# motordriver-v4_0_power-stage.net
KiCad netlist of a schematic drawn in Altium Designer
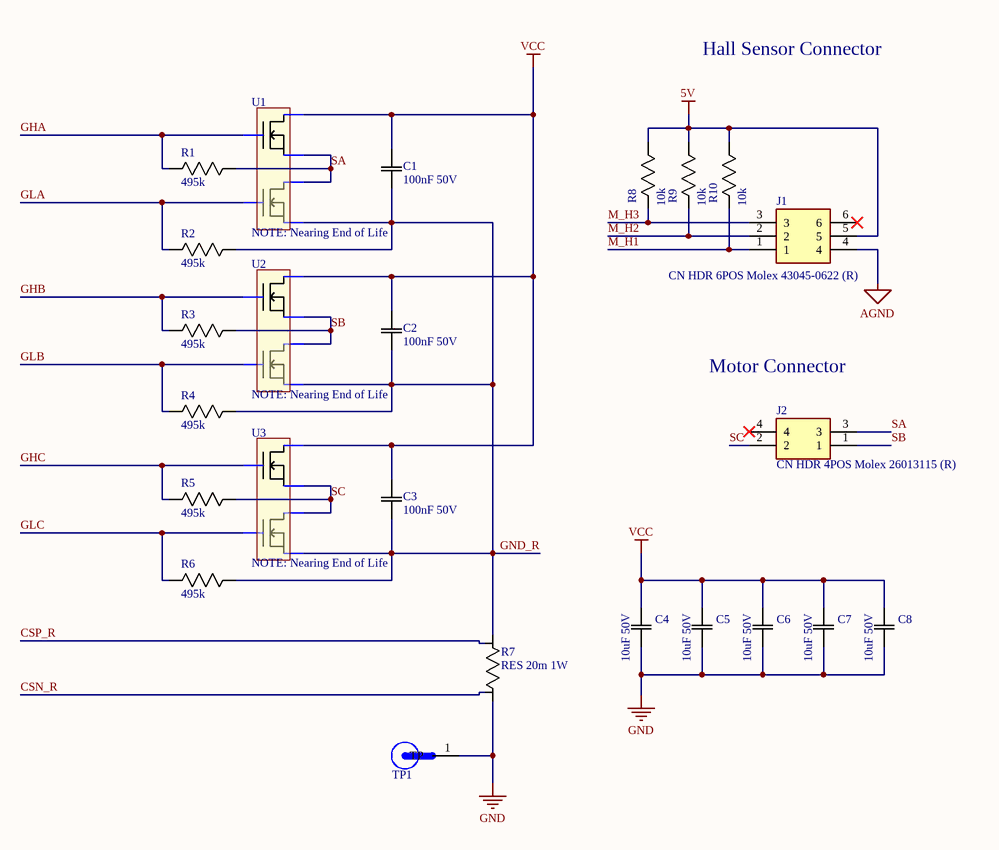
[diagram p0: motordriver-v4.0_power-stage.SchDoc]

(export (version "E")
  (design (tool "Eeschema 10.0.6"))
  (components
    (comp (ref "C1")
      (value "100nF 50V")
      (footprint "0603")
      (description "CAP CER 0.1UF 50V X7R 0805")
      (fields (field (name "TOLERANCE") "10%"))
      (libsource (lib "AltiumLibraries") (part "CAP 100nF 50V"))
    )
    (comp (ref "C2")
      (value "100nF 50V")
      (footprint "0603")
      (description "CAP CER 0.1UF 50V X7R 0805")
      (fields (field (name "TOLERANCE") "10%"))
      (libsource (lib "AltiumLibraries") (part "CAP 100nF 50V"))
    )
    (comp (ref "C3")
      (value "100nF 50V")
      (footprint "0603")
      (description "CAP CER 0.1UF 50V X7R 0805")
      (fields (field (name "TOLERANCE") "10%"))
      (libsource (lib "AltiumLibraries") (part "CAP 100nF 50V"))
    )
    (comp (ref "C4")
      (value "10uF 50V")
      (footprint "0805")
      (description "CAP CER 10UF 50V X7R")
      (fields (field (name "TOLERANCE") "10%"))
      (libsource (lib "AltiumLibraries") (part "CAP 10uF 50V"))
    )
    (comp (ref "C5")
      (value "10uF 50V")
      (footprint "0805")
      (description "CAP CER 10UF 50V X7R")
      (fields (field (name "TOLERANCE") "10%"))
      (libsource (lib "AltiumLibraries") (part "CAP 10uF 50V"))
    )
    (comp (ref "C6")
      (value "10uF 50V")
      (footprint "0805")
      (description "CAP CER 10UF 50V X7R")
      (fields (field (name "TOLERANCE") "10%"))
      (libsource (lib "AltiumLibraries") (part "CAP 10uF 50V"))
    )
    (comp (ref "C7")
      (value "10uF 50V")
      (footprint "0805")
      (description "CAP CER 10UF 50V X7R")
      (fields (field (name "TOLERANCE") "10%"))
      (libsource (lib "AltiumLibraries") (part "CAP 10uF 50V"))
    )
    (comp (ref "C8")
      (value "10uF 50V")
      (footprint "0805")
      (description "CAP CER 10UF 50V X7R")
      (fields (field (name "TOLERANCE") "10%"))
      (libsource (lib "AltiumLibraries") (part "CAP 10uF 50V"))
    )
    (comp (ref "J1")
      (value "CN HDR 6POS Molex 43045-0622 (R)")
      (footprint "430450622")
      (description "Molex 43045-0622 6POS Microfit\r\ndual row, right angle")
      (libsource (lib "AltiumLibraries") (part "CN HDR 6POS Molex 43045-0622 (R)"))
    )
    (comp (ref "J2")
      (value "CN HDR 4POS Molex 26013115 (R)")
      (footprint "26013115")
      (description "Molex 26013115 4POS Minifit\r\ndual row, right angle")
      (libsource (lib "AltiumLibraries") (part "CN HDR 4POS Molex 26013115 (R)"))
    )
    (comp (ref "R1")
      (value "495k")
      (footprint "0603")
      (description "RES SMD 499K OHM 1% 1/8W 0805")
      (fields
        (field (name "MANUFACTURER") "Yageo")
        (field (name "MANUFACTURER PART NUMBER") "RC0805FR-07499KL")
      )
      (libsource (lib "AltiumLibraries") (part "RES 495k 1/8W"))
    )
    (comp (ref "R2")
      (value "495k")
      (footprint "0603")
      (description "RES SMD 499K OHM 1% 1/8W 0805")
      (fields
        (field (name "MANUFACTURER") "Yageo")
        (field (name "MANUFACTURER PART NUMBER") "RC0805FR-07499KL")
      )
      (libsource (lib "AltiumLibraries") (part "RES 495k 1/8W"))
    )
    (comp (ref "R3")
      (value "495k")
      (footprint "0603")
      (description "RES SMD 499K OHM 1% 1/8W 0805")
      (fields
        (field (name "MANUFACTURER") "Yageo")
        (field (name "MANUFACTURER PART NUMBER") "RC0805FR-07499KL")
      )
      (libsource (lib "AltiumLibraries") (part "RES 495k 1/8W"))
    )
    (comp (ref "R4")
      (value "495k")
      (footprint "0603")
      (description "RES SMD 499K OHM 1% 1/8W 0805")
      (fields
        (field (name "MANUFACTURER") "Yageo")
        (field (name "MANUFACTURER PART NUMBER") "RC0805FR-07499KL")
      )
      (libsource (lib "AltiumLibraries") (part "RES 495k 1/8W"))
    )
    (comp (ref "R5")
      (value "495k")
      (footprint "0603")
      (description "RES SMD 499K OHM 1% 1/8W 0805")
      (fields
        (field (name "MANUFACTURER") "Yageo")
        (field (name "MANUFACTURER PART NUMBER") "RC0805FR-07499KL")
      )
      (libsource (lib "AltiumLibraries") (part "RES 495k 1/8W"))
    )
    (comp (ref "R6")
      (value "495k")
      (footprint "0603")
      (description "RES SMD 499K OHM 1% 1/8W 0805")
      (fields
        (field (name "MANUFACTURER") "Yageo")
        (field (name "MANUFACTURER PART NUMBER") "RC0805FR-07499KL")
      )
      (libsource (lib "AltiumLibraries") (part "RES 495k 1/8W"))
    )
    (comp (ref "R7")
      (value "RES 20m 1W")
      (footprint "1206 - Sense")
      (description "RES SMD 0.02 OHM 1% 1W 1206")
      (libsource (lib "AltiumLibraries") (part "RES 20m 1W"))
    )
    (comp (ref "R8")
      (value "10k")
      (footprint "0603")
      (description "RES SMD 10K OHM 1% 1/8W 0805")
      (fields (field (name "TOLERANCE") "1%"))
      (libsource (lib "") (part "RES 10k 1/8W - 1%_1"))
    )
    (comp (ref "R9")
      (value "10k")
      (footprint "0603")
      (description "RES SMD 10K OHM 1% 1/8W 0805")
      (fields (field (name "TOLERANCE") "1%"))
      (libsource (lib "AltiumLibraries") (part "RES 10k 1/8W - 1%"))
    )
    (comp (ref "R10")
      (value "10k")
      (footprint "0603")
      (description "RES SMD 10K OHM 1% 1/8W 0805")
      (fields (field (name "TOLERANCE") "1%"))
      (libsource (lib "AltiumLibraries") (part "RES 10k 1/8W - 1%"))
    )
    (comp (ref "TP1")
      (value "Test Point - 5019")
      (footprint "TP380X203")
      (description "PC Test Point, Miniature Phosphor Bronze, Silver Plating Surface Mount Mounting Type")
      (fields (field (name "MP") "5019") (field (name "MF") "Keystone Electronics"))
      (libsource (lib "AltiumLibraries") (part "Test Point - 5019"))
    )
    (comp (ref "U1")
      (value "NOTE: Nearing End of Life")
      (footprint "PG-TDSON-8-10")
      (description "MOSFET N+N 60V 20A")
      (fields (field (name "MF") "Infineon Technologies"))
      (libsource (lib "AltiumLibraries") (part "MOSFET IPG20N06S4-15A"))
    )
    (comp (ref "U2")
      (value "NOTE: Nearing End of Life")
      (footprint "PG-TDSON-8-10")
      (description "MOSFET N+N 60V 20A")
      (fields (field (name "MF") "Infineon Technologies"))
      (libsource (lib "AltiumLibraries") (part "MOSFET IPG20N06S4-15A"))
    )
    (comp (ref "U3")
      (value "NOTE: Nearing End of Life")
      (footprint "PG-TDSON-8-10")
      (description "MOSFET N+N 60V 20A")
      (fields (field (name "MF") "Infineon Technologies"))
      (libsource (lib "AltiumLibraries") (part "MOSFET IPG20N06S4-15A"))
    )
  )
  (nets
    (net (code "1") (name "/CSN_R") (class "Default")
      (node (ref "R7") (pin "4") (pinfunction "4_4") (pintype "passive"))
    )
    (net (code "2") (name "/CSP_R") (class "Default")
      (node (ref "R7") (pin "3") (pinfunction "3_3") (pintype "passive"))
    )
    (net (code "3") (name "/GHA") (class "Default")
      (node (ref "R1") (pin "2") (pinfunction "R2_2") (pintype "passive"))
      (node (ref "U1") (pin "2") (pinfunction "G1_2") (pintype "passive"))
    )
    (net (code "4") (name "/GHB") (class "Default")
      (node (ref "R3") (pin "2") (pinfunction "R2_2") (pintype "passive"))
      (node (ref "U2") (pin "2") (pinfunction "G1_2") (pintype "passive"))
    )
    (net (code "5") (name "/GHC") (class "Default")
      (node (ref "R5") (pin "2") (pinfunction "R2_2") (pintype "passive"))
      (node (ref "U3") (pin "2") (pinfunction "G1_2") (pintype "passive"))
    )
    (net (code "6") (name "/GLA") (class "Default")
      (node (ref "R2") (pin "2") (pinfunction "R2_2") (pintype "passive"))
      (node (ref "U1") (pin "4") (pinfunction "G2_4") (pintype "passive"))
    )
    (net (code "7") (name "/GLB") (class "Default")
      (node (ref "R4") (pin "2") (pinfunction "R2_2") (pintype "passive"))
      (node (ref "U2") (pin "4") (pinfunction "G2_4") (pintype "passive"))
    )
    (net (code "8") (name "/GLC") (class "Default")
      (node (ref "R6") (pin "2") (pinfunction "R2_2") (pintype "passive"))
      (node (ref "U3") (pin "4") (pinfunction "G2_4") (pintype "passive"))
    )
    (net (code "9") (name "/GND_R") (class "Default")
      (node (ref "C1") (pin "1") (pinfunction "C1_1") (pintype "passive"))
      (node (ref "C2") (pin "1") (pinfunction "C1_1") (pintype "passive"))
      (node (ref "C3") (pin "1") (pinfunction "C1_1") (pintype "passive"))
      (node (ref "R2") (pin "1") (pinfunction "R1_1") (pintype "passive"))
      (node (ref "R4") (pin "1") (pinfunction "R1_1") (pintype "passive"))
      (node (ref "R6") (pin "1") (pinfunction "R1_1") (pintype "passive"))
      (node (ref "R7") (pin "1") (pinfunction "R1_1") (pintype "passive"))
      (node (ref "U1") (pin "3") (pinfunction "S2_3") (pintype "passive"))
      (node (ref "U2") (pin "3") (pinfunction "S2_3") (pintype "passive"))
      (node (ref "U3") (pin "3") (pinfunction "S2_3") (pintype "passive"))
    )
    (net (code "10") (name "/M_H1") (class "Default")
      (node (ref "J1") (pin "1") (pinfunction "1_1") (pintype "passive"))
      (node (ref "R10") (pin "2") (pinfunction "R2_2") (pintype "passive"))
    )
    (net (code "11") (name "/M_H2") (class "Default")
      (node (ref "J1") (pin "2") (pinfunction "2_2") (pintype "passive"))
      (node (ref "R9") (pin "2") (pinfunction "R2_2") (pintype "passive"))
    )
    (net (code "12") (name "/M_H3") (class "Default")
      (node (ref "J1") (pin "3") (pinfunction "3_3") (pintype "passive"))
      (node (ref "R8") (pin "2") (pinfunction "R2_2") (pintype "passive"))
    )
    (net (code "13") (name "/SA") (class "Default")
      (node (ref "J2") (pin "3") (pinfunction "3_3") (pintype "passive"))
      (node (ref "R1") (pin "1") (pinfunction "R1_1") (pintype "passive"))
      (node (ref "U1") (pin "1") (pinfunction "S1_1") (pintype "passive"))
      (node (ref "U1") (pin "6") (pinfunction "D2_6") (pintype "passive"))
    )
    (net (code "14") (name "/SB") (class "Default")
      (node (ref "J2") (pin "1") (pinfunction "1_1") (pintype "passive"))
      (node (ref "R3") (pin "1") (pinfunction "R1_1") (pintype "passive"))
      (node (ref "U2") (pin "1") (pinfunction "S1_1") (pintype "passive"))
      (node (ref "U2") (pin "6") (pinfunction "D2_6") (pintype "passive"))
    )
    (net (code "15") (name "/SC") (class "Default")
      (node (ref "J2") (pin "2") (pinfunction "2_2") (pintype "passive"))
      (node (ref "R5") (pin "1") (pinfunction "R1_1") (pintype "passive"))
      (node (ref "U3") (pin "1") (pinfunction "S1_1") (pintype "passive"))
      (node (ref "U3") (pin "6") (pinfunction "D2_6") (pintype "passive"))
    )
    (net (code "16") (name "5V") (class "Default")
      (node (ref "J1") (pin "5") (pinfunction "5_5") (pintype "passive"))
      (node (ref "R10") (pin "1") (pinfunction "R1_1") (pintype "passive"))
      (node (ref "R8") (pin "1") (pinfunction "R1_1") (pintype "passive"))
      (node (ref "R9") (pin "1") (pinfunction "R1_1") (pintype "passive"))
    )
    (net (code "17") (name "AGND") (class "Default")
      (node (ref "J1") (pin "4") (pinfunction "4_4") (pintype "passive"))
    )
    (net (code "18") (name "GND") (class "Default")
      (node (ref "C4") (pin "2") (pinfunction "C2_2") (pintype "passive"))
      (node (ref "C5") (pin "2") (pinfunction "C2_2") (pintype "passive"))
      (node (ref "C6") (pin "2") (pinfunction "C2_2") (pintype "passive"))
      (node (ref "C7") (pin "2") (pinfunction "C2_2") (pintype "passive"))
      (node (ref "C8") (pin "2") (pinfunction "C2_2") (pintype "passive"))
      (node (ref "R7") (pin "2") (pinfunction "R2_2") (pintype "passive"))
      (node (ref "TP1") (pin "1") (pinfunction "TP_1") (pintype "passive"))
    )
    (net (code "19") (name "VCC") (class "Default")
      (node (ref "C1") (pin "2") (pinfunction "C2_2") (pintype "passive"))
      (node (ref "C2") (pin "2") (pinfunction "C2_2") (pintype "passive"))
      (node (ref "C3") (pin "2") (pinfunction "C2_2") (pintype "passive"))
      (node (ref "C4") (pin "1") (pinfunction "C1_1") (pintype "passive"))
      (node (ref "C5") (pin "1") (pinfunction "C1_1") (pintype "passive"))
      (node (ref "C6") (pin "1") (pinfunction "C1_1") (pintype "passive"))
      (node (ref "C7") (pin "1") (pinfunction "C1_1") (pintype "passive"))
      (node (ref "C8") (pin "1") (pinfunction "C1_1") (pintype "passive"))
      (node (ref "U1") (pin "8") (pinfunction "D1_8") (pintype "passive"))
      (node (ref "U2") (pin "8") (pinfunction "D1_8") (pintype "passive"))
      (node (ref "U3") (pin "8") (pinfunction "D1_8") (pintype "passive"))
    )
    (net (code "20") (name "unconnected-(J1-Pad6)") (class "Default")
      (node (ref "J1") (pin "6") (pinfunction "6_6") (pintype "passive+no_connect"))
    )
    (net (code "21") (name "unconnected-(J2-Pad4)") (class "Default")
      (node (ref "J2") (pin "4") (pinfunction "4_4") (pintype "passive+no_connect"))
    )
  )
)
